# ManitoBoardv_5.net
KiCad netlist of a schematic drawn in EAGLE
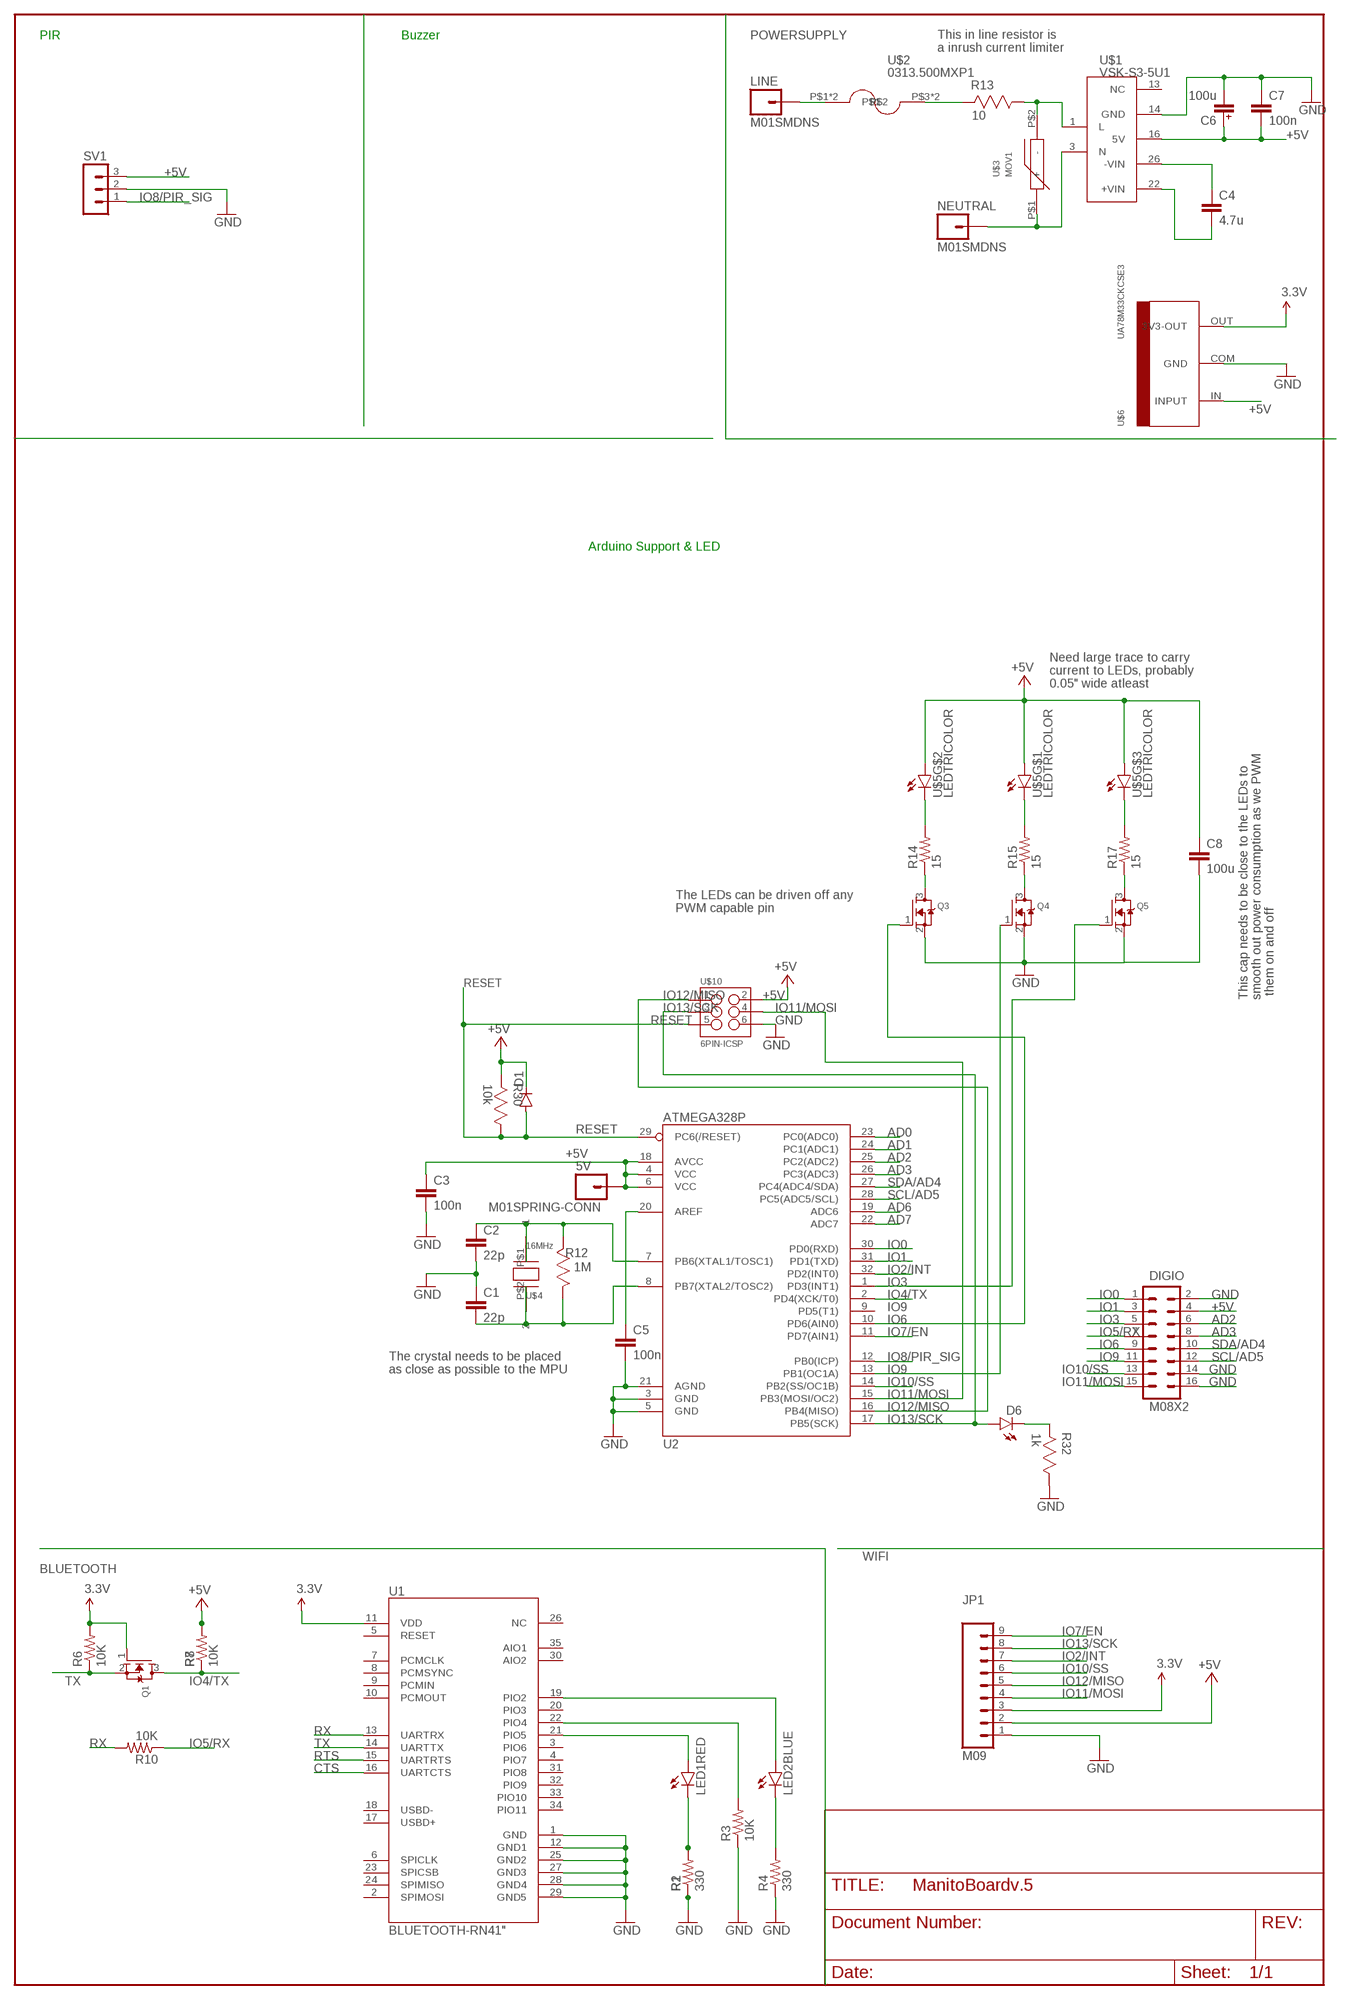
[diagram p0: schematic, sheet 1]

(export (version "E")
  (design (tool "Eeschema 10.0.6"))
  (components
    (comp (ref "5V")
      (value "M01SPRING-CONN")
      (footprint "eagle-import:SPRING-CONNECTOR")
      (libsource (lib "eagle-import") (part "M01SPRING-CONN"))
    )
    (comp (ref "C1")
      (value "22p")
      (footprint "eagle-import:0603-CAP")
      (libsource (lib "eagle-import") (part "CAP0603-CAP"))
    )
    (comp (ref "C2")
      (value "22p")
      (footprint "eagle-import:0603-CAP")
      (libsource (lib "eagle-import") (part "CAP0603-CAP"))
    )
    (comp (ref "C3")
      (value "100n")
      (footprint "eagle-import:0603-CAP")
      (libsource (lib "eagle-import") (part "CAP0603-CAP"))
    )
    (comp (ref "C4")
      (value "4.7u")
      (footprint "eagle-import:0603-CAP")
      (libsource (lib "eagle-import") (part "CAP0603-CAP"))
    )
    (comp (ref "C5")
      (value "100n")
      (footprint "eagle-import:0603-CAP")
      (libsource (lib "eagle-import") (part "CAP0603-CAP"))
    )
    (comp (ref "C6")
      (value "100u")
      (footprint "eagle-import:WXSERIES-SMDCAP")
      (libsource (lib "eagle-import") (part "SMDCAP1"))
    )
    (comp (ref "C7")
      (value "100n")
      (footprint "eagle-import:0603-CAP")
      (libsource (lib "eagle-import") (part "CAP0603-CAP"))
    )
    (comp (ref "C8")
      (value "100u")
      (footprint "eagle-import:0603-CAP")
      (libsource (lib "eagle-import") (part "CAP0603-CAP"))
    )
    (comp (ref "D1")
      (value "DIODE1N4148")
      (footprint "eagle-import:DIODE-1N4148")
      (libsource (lib "eagle-import") (part "DIODE1N4148"))
    )
    (comp (ref "D6")
      (value "LED-YELLOW0603")
      (footprint "eagle-import:LED-0603")
      (libsource (lib "eagle-import") (part "LED-YELLOW0603"))
    )
    (comp (ref "DIGIO")
      (value "M08X2")
      (footprint "eagle-import:2X8")
      (libsource (lib "eagle-import") (part "M08X2"))
    )
    (comp (ref "JP1")
      (value "M09")
      (footprint "eagle-import:1X09")
      (libsource (lib "eagle-import") (part "M09"))
    )
    (comp (ref "LED1RED")
      (value "LED3MM")
      (footprint "eagle-import:LED3MM")
      (libsource (lib "eagle-import") (part "LED3MM"))
    )
    (comp (ref "LED2BLUE")
      (value "LED3MM")
      (footprint "eagle-import:LED3MM")
      (libsource (lib "eagle-import") (part "LED3MM"))
    )
    (comp (ref "LINE")
      (value "M01SMDNS")
      (footprint "eagle-import:1X01NS")
      (libsource (lib "eagle-import") (part "M01SMDNS"))
    )
    (comp (ref "NEUTRAL")
      (value "M01SMDNS")
      (footprint "eagle-import:1X01NS")
      (libsource (lib "eagle-import") (part "M01SMDNS"))
    )
    (comp (ref "Q1")
      (value "MOSFET-NREFLOW")
      (footprint "eagle-import:SOT23")
      (libsource (lib "eagle-import") (part "adafruit_MOSFET-NREFLOW"))
    )
    (comp (ref "Q3")
      (value "MOSFET-NREFLOW")
      (footprint "eagle-import:SOT23")
      (libsource (lib "eagle-import") (part "MOSFET-NREFLOW"))
    )
    (comp (ref "Q4")
      (value "MOSFET-NREFLOW")
      (footprint "eagle-import:SOT23")
      (libsource (lib "eagle-import") (part "MOSFET-NREFLOW"))
    )
    (comp (ref "Q5")
      (value "MOSFET-NREFLOW")
      (footprint "eagle-import:SOT23")
      (libsource (lib "eagle-import") (part "MOSFET-NREFLOW"))
    )
    (comp (ref "R1")
      (value "RESISTORPTH-1/4W")
      (footprint "eagle-import:AXIAL-0.4")
      (libsource (lib "eagle-import") (part "RESISTORPTH-1/4W"))
    )
    (comp (ref "R2")
      (value "330")
      (footprint "eagle-import:AXIAL-0.4")
      (libsource (lib "eagle-import") (part "RESISTORPTH-1/4W"))
    )
    (comp (ref "R3")
      (value "10K")
      (footprint "eagle-import:AXIAL-0.4")
      (libsource (lib "eagle-import") (part "RESISTORPTH-1/4W"))
    )
    (comp (ref "R4")
      (value "330")
      (footprint "eagle-import:AXIAL-0.4")
      (libsource (lib "eagle-import") (part "RESISTORPTH-1/4W"))
    )
    (comp (ref "R6")
      (value "10K")
      (footprint "eagle-import:AXIAL-0.5")
      (libsource (lib "eagle-import") (part "RESISTORPTH-1/2W"))
    )
    (comp (ref "R7")
      (value "RESISTORPTH-1/2W")
      (footprint "eagle-import:AXIAL-0.5")
      (libsource (lib "eagle-import") (part "RESISTORPTH-1/2W"))
    )
    (comp (ref "R8")
      (value "10K")
      (footprint "eagle-import:AXIAL-0.5")
      (libsource (lib "eagle-import") (part "RESISTORPTH-1/2W"))
    )
    (comp (ref "R10")
      (value "10K")
      (footprint "eagle-import:AXIAL-0.5")
      (libsource (lib "eagle-import") (part "RESISTORPTH-1/2W"))
    )
    (comp (ref "R12")
      (value "1M")
      (footprint "eagle-import:0603RESISTOR")
      (fields (field (name "MPN") "CRCW06031K21FKEA") (field (name "TOLERANCE") "± 1.0 %"))
      (libsource (lib "eagle-import") (part "0603RESISTOR1"))
    )
    (comp (ref "R13")
      (value "10")
      (footprint "eagle-import:0603RESISTOR")
      (fields (field (name "MPN") "CRCW06031K21FKEA") (field (name "TOLERANCE") "± 1.0 %"))
      (libsource (lib "eagle-import") (part "0603RESISTOR1"))
    )
    (comp (ref "R14")
      (value "15")
      (footprint "eagle-import:AXIAL-0.6")
      (libsource (lib "eagle-import") (part "RESISTORPTH-1W"))
    )
    (comp (ref "R15")
      (value "15")
      (footprint "eagle-import:AXIAL-0.6")
      (libsource (lib "eagle-import") (part "RESISTORPTH-1W"))
    )
    (comp (ref "R17")
      (value "15")
      (footprint "eagle-import:AXIAL-0.6")
      (libsource (lib "eagle-import") (part "RESISTORPTH-1W"))
    )
    (comp (ref "R30")
      (value "10k")
      (footprint "eagle-import:0603RESISTOR")
      (fields (field (name "MPN") "CRCW06031K21FKEA") (field (name "TOLERANCE") "± 1.0 %"))
      (libsource (lib "eagle-import") (part "0603RESISTOR1"))
    )
    (comp (ref "R32")
      (value "1k")
      (footprint "eagle-import:0603RESISTOR")
      (fields (field (name "MPN") "CRCW06031K21FKEA") (field (name "TOLERANCE") "± 1.0 %"))
      (libsource (lib "eagle-import") (part "0603RESISTOR1"))
    )
    (comp (ref "SV1")
      (value "MA03-1")
      (footprint "eagle-import:MA03-1")
      (libsource (lib "eagle-import") (part "MA03-1"))
    )
    (comp (ref "U$1")
      (value "VSK-S3-5U1")
      (footprint "eagle-import:VSK-S3-DCAC")
      (libsource (lib "eagle-import") (part "VSK-S3-5U1"))
    )
    (comp (ref "U$2")
      (value "0313.500MXP1")
      (footprint "eagle-import:FUSEHOLDER0.25IN")
      (libsource (lib "eagle-import") (part "0313.500MXP1"))
    )
    (comp (ref "U$3")
      (value "MOV1")
      (footprint "eagle-import:MOV")
      (libsource (lib "eagle-import") (part "MOV1"))
    )
    (comp (ref "U$4")
      (value "16MHz")
      (footprint "eagle-import:SMDCRYSTAL")
      (libsource (lib "eagle-import") (part "SMDCRYSTAL"))
    )
    (comp (ref "U$5")
      (value "LEDTRICOLOR")
      (footprint "eagle-import:TRICOLORLED")
      (libsource (lib "eagle-import") (part "LEDTRICOLOR"))
    )
    (comp (ref "U$6")
      (value "UA78M33CKCSE3")
      (footprint "eagle-import:TO220")
      (libsource (lib "eagle-import") (part "UA78M33CKCSE3"))
    )
    (comp (ref "U$10")
      (value "6PIN-ICSP")
      (footprint "eagle-import:2X3-ICSP")
      (libsource (lib "eagle-import") (part "6PIN-ICSP"))
    )
    (comp (ref "U1")
      (value "BLUETOOTH-RN41\"")
      (footprint "eagle-import:RN41")
      (libsource (lib "eagle-import") (part "BLUETOOTH-RN41{dblquote}"))
    )
    (comp (ref "U2")
      (value "ATMEGA328P")
      (footprint "eagle-import:TQFP32-08")
      (libsource (lib "eagle-import") (part "ATMEGA328_SMT"))
    )
  )
  (nets
    (net (code "1") (name "+5V") (class "Default")
      (node (ref "5V") (pin "P$2") (pinfunction "1_P$2") (pintype "passive"))
      (node (ref "C3") (pin "1") (pinfunction "1_1") (pintype "passive"))
      (node (ref "C6") (pin "POS") (pinfunction "POS_POS") (pintype "passive"))
      (node (ref "C7") (pin "2") (pinfunction "2_2") (pintype "passive"))
      (node (ref "C8") (pin "1") (pinfunction "1_1") (pintype "passive"))
      (node (ref "D1") (pin "C") (pinfunction "C_C") (pintype "passive"))
      (node (ref "DIGIO") (pin "4") (pinfunction "4_4") (pintype "passive"))
      (node (ref "JP1") (pin "2") (pinfunction "2_2") (pintype "passive"))
      (node (ref "R30") (pin "2") (pinfunction "2_2") (pintype "passive"))
      (node (ref "R7") (pin "P$2") (pinfunction "2_P$2") (pintype "passive"))
      (node (ref "R8") (pin "P$2") (pinfunction "2_P$2") (pintype "passive"))
      (node (ref "SV1") (pin "3") (pinfunction "3_3") (pintype "passive"))
      (node (ref "U$1") (pin "16") (pinfunction "5V_16") (pintype "bidirectional"))
      (node (ref "U$10") (pin "2") (pinfunction "+5V_2") (pintype "power_in"))
      (node (ref "U$5") (pin "A1") (pinfunction "A_A1") (pintype "passive"))
      (node (ref "U$5") (pin "A2") (pinfunction "A_A2") (pintype "passive"))
      (node (ref "U$5") (pin "A3") (pinfunction "A_A3") (pintype "passive"))
      (node (ref "U$6") (pin "IN") (pinfunction "INPUT_IN") (pintype "power_in"))
      (node (ref "U2") (pin "18") (pinfunction "AVCC_18") (pintype "bidirectional"))
      (node (ref "U2") (pin "4") (pinfunction "VCC_4") (pintype "bidirectional"))
      (node (ref "U2") (pin "6") (pinfunction "VCC_6") (pintype "bidirectional"))
    )
    (net (code "2") (name "/AD0") (class "Default")
      (node (ref "U2") (pin "23") (pinfunction "PC0(ADC0)_23") (pintype "bidirectional"))
    )
    (net (code "3") (name "/AD1") (class "Default")
      (node (ref "U2") (pin "24") (pinfunction "PC1(ADC1)_24") (pintype "bidirectional"))
    )
    (net (code "4") (name "/AD2") (class "Default")
      (node (ref "DIGIO") (pin "6") (pinfunction "6_6") (pintype "passive"))
      (node (ref "U2") (pin "25") (pinfunction "PC2(ADC2)_25") (pintype "bidirectional"))
    )
    (net (code "5") (name "/AD3") (class "Default")
      (node (ref "DIGIO") (pin "8") (pinfunction "8_8") (pintype "passive"))
      (node (ref "U2") (pin "26") (pinfunction "PC3(ADC3)_26") (pintype "bidirectional"))
    )
    (net (code "6") (name "/AD6") (class "Default")
      (node (ref "U2") (pin "19") (pinfunction "ADC6_19") (pintype "bidirectional"))
    )
    (net (code "7") (name "/AD7") (class "Default")
      (node (ref "U2") (pin "22") (pinfunction "ADC7_22") (pintype "bidirectional"))
    )
    (net (code "9") (name "/CTS") (class "Default")
      (node (ref "U1") (pin "16") (pinfunction "UARTCTS_16") (pintype "bidirectional"))
    )
    (net (code "10") (name "/IO0") (class "Default")
      (node (ref "DIGIO") (pin "1") (pinfunction "1_1") (pintype "passive"))
      (node (ref "U2") (pin "30") (pinfunction "PD0(RXD)_30") (pintype "bidirectional"))
    )
    (net (code "11") (name "/IO1") (class "Default")
      (node (ref "DIGIO") (pin "3") (pinfunction "3_3") (pintype "passive"))
      (node (ref "U2") (pin "31") (pinfunction "PD1(TXD)_31") (pintype "bidirectional"))
    )
    (net (code "12") (name "/IO2{slash}INT") (class "Default")
      (node (ref "JP1") (pin "7") (pinfunction "7_7") (pintype "passive"))
      (node (ref "U2") (pin "32") (pinfunction "PD2(INT0)_32") (pintype "bidirectional"))
    )
    (net (code "13") (name "/IO3") (class "Default")
      (node (ref "DIGIO") (pin "5") (pinfunction "5_5") (pintype "passive"))
      (node (ref "Q5") (pin "1") (pinfunction "G_1") (pintype "bidirectional"))
      (node (ref "U2") (pin "1") (pinfunction "PD3(INT1)_1") (pintype "bidirectional"))
    )
    (net (code "14") (name "/IO4{slash}TX") (class "Default")
      (node (ref "Q1") (pin "3") (pinfunction "D_3") (pintype "bidirectional"))
      (node (ref "R7") (pin "P$1") (pinfunction "1_P$1") (pintype "passive"))
      (node (ref "R8") (pin "P$1") (pinfunction "1_P$1") (pintype "passive"))
      (node (ref "U2") (pin "2") (pinfunction "PD4(XCK/T0)_2") (pintype "bidirectional"))
    )
    (net (code "15") (name "/IO5{slash}RX") (class "Default")
      (node (ref "DIGIO") (pin "7") (pinfunction "7_7") (pintype "passive"))
      (node (ref "R10") (pin "P$1") (pinfunction "1_P$1") (pintype "passive"))
    )
    (net (code "16") (name "/IO6") (class "Default")
      (node (ref "DIGIO") (pin "9") (pinfunction "9_9") (pintype "passive"))
      (node (ref "Q3") (pin "1") (pinfunction "G_1") (pintype "bidirectional"))
      (node (ref "U2") (pin "10") (pinfunction "PD6(AIN0)_10") (pintype "bidirectional"))
    )
    (net (code "17") (name "/IO7{slash}EN") (class "Default")
      (node (ref "JP1") (pin "9") (pinfunction "9_9") (pintype "passive"))
      (node (ref "U2") (pin "11") (pinfunction "PD7(AIN1)_11") (pintype "bidirectional"))
    )
    (net (code "18") (name "/IO8{slash}PIR_SIG") (class "Default")
      (node (ref "SV1") (pin "1") (pinfunction "1_1") (pintype "passive"))
      (node (ref "U2") (pin "12") (pinfunction "PB0(ICP)_12") (pintype "bidirectional"))
    )
    (net (code "19") (name "/IO9") (class "Default")
      (node (ref "DIGIO") (pin "11") (pinfunction "11_11") (pintype "passive"))
      (node (ref "Q4") (pin "1") (pinfunction "G_1") (pintype "bidirectional"))
      (node (ref "U2") (pin "13") (pinfunction "PB1(OC1A)_13") (pintype "bidirectional"))
    )
    (net (code "20") (name "/IO10{slash}SS") (class "Default")
      (node (ref "DIGIO") (pin "13") (pinfunction "13_13") (pintype "passive"))
      (node (ref "JP1") (pin "6") (pinfunction "6_6") (pintype "passive"))
      (node (ref "U2") (pin "14") (pinfunction "PB2(SS/OC1B)_14") (pintype "bidirectional"))
    )
    (net (code "21") (name "/IO11{slash}MOSI") (class "Default")
      (node (ref "DIGIO") (pin "15") (pinfunction "15_15") (pintype "passive"))
      (node (ref "JP1") (pin "4") (pinfunction "4_4") (pintype "passive"))
      (node (ref "U$10") (pin "4") (pinfunction "MOSI_4") (pintype "bidirectional"))
      (node (ref "U2") (pin "15") (pinfunction "PB3(MOSI/OC2)_15") (pintype "bidirectional"))
    )
    (net (code "22") (name "/IO12{slash}MISO") (class "Default")
      (node (ref "JP1") (pin "5") (pinfunction "5_5") (pintype "passive"))
      (node (ref "U$10") (pin "1") (pinfunction "MISO_1") (pintype "bidirectional"))
      (node (ref "U2") (pin "16") (pinfunction "PB4(MISO)_16") (pintype "bidirectional"))
    )
    (net (code "23") (name "/IO13{slash}SCK") (class "Default")
      (node (ref "D6") (pin "A") (pinfunction "A_A") (pintype "passive"))
      (node (ref "JP1") (pin "8") (pinfunction "8_8") (pintype "passive"))
      (node (ref "U$10") (pin "3") (pinfunction "SCK_3") (pintype "bidirectional"))
      (node (ref "U2") (pin "17") (pinfunction "PB5(SCK)_17") (pintype "bidirectional"))
    )
    (net (code "25") (name "/RESET") (class "Default")
      (node (ref "D1") (pin "A") (pinfunction "A_A") (pintype "passive"))
      (node (ref "R30") (pin "1") (pinfunction "1_1") (pintype "passive"))
      (node (ref "U$10") (pin "5") (pinfunction "RESET_5") (pintype "bidirectional"))
      (node (ref "U2") (pin "29") (pinfunction "PC6(/RESET)_29") (pintype "bidirectional"))
    )
    (net (code "26") (name "/RTS") (class "Default")
      (node (ref "U1") (pin "15") (pinfunction "UARTRTS_15") (pintype "bidirectional"))
    )
    (net (code "27") (name "/RX") (class "Default")
      (node (ref "R10") (pin "P$2") (pinfunction "2_P$2") (pintype "passive"))
      (node (ref "U1") (pin "13") (pinfunction "UARTRX_13") (pintype "bidirectional"))
    )
    (net (code "28") (name "/SCL{slash}AD5") (class "Default")
      (node (ref "DIGIO") (pin "12") (pinfunction "12_12") (pintype "passive"))
      (node (ref "U2") (pin "28") (pinfunction "PC5(ADC5/SCL)_28") (pintype "bidirectional"))
    )
    (net (code "29") (name "/SDA{slash}AD4") (class "Default")
      (node (ref "DIGIO") (pin "10") (pinfunction "10_10") (pintype "passive"))
      (node (ref "U2") (pin "27") (pinfunction "PC4(ADC4/SDA)_27") (pintype "bidirectional"))
    )
    (net (code "30") (name "/TX") (class "Default")
      (node (ref "Q1") (pin "2") (pinfunction "S_2") (pintype "bidirectional"))
      (node (ref "R6") (pin "P$1") (pinfunction "1_P$1") (pintype "passive"))
      (node (ref "U1") (pin "14") (pinfunction "UARTTX_14") (pintype "bidirectional"))
    )
    (net (code "32") (name "3.3V") (class "Default")
      (node (ref "JP1") (pin "3") (pinfunction "3_3") (pintype "passive"))
      (node (ref "Q1") (pin "1") (pinfunction "G_1") (pintype "bidirectional"))
      (node (ref "R6") (pin "P$2") (pinfunction "2_P$2") (pintype "passive"))
      (node (ref "U$6") (pin "OUT") (pinfunction "3V3-OUT_OUT") (pintype "power_in"))
      (node (ref "U1") (pin "11") (pinfunction "VDD_11") (pintype "bidirectional"))
    )
    (net (code "33") (name "GND") (class "Default")
      (node (ref "C1") (pin "1") (pinfunction "1_1") (pintype "passive"))
      (node (ref "C2") (pin "2") (pinfunction "2_2") (pintype "passive"))
      (node (ref "C3") (pin "2") (pinfunction "2_2") (pintype "passive"))
      (node (ref "C5") (pin "2") (pinfunction "2_2") (pintype "passive"))
      (node (ref "C6") (pin "NEG") (pinfunction "NEG_NEG") (pintype "passive"))
      (node (ref "C7") (pin "1") (pinfunction "1_1") (pintype "passive"))
      (node (ref "C8") (pin "2") (pinfunction "2_2") (pintype "passive"))
      (node (ref "DIGIO") (pin "14") (pinfunction "14_14") (pintype "passive"))
      (node (ref "DIGIO") (pin "16") (pinfunction "16_16") (pintype "passive"))
      (node (ref "DIGIO") (pin "2") (pinfunction "2_2") (pintype "passive"))
      (node (ref "JP1") (pin "1") (pinfunction "1_1") (pintype "passive"))
      (node (ref "Q3") (pin "2") (pinfunction "S_2") (pintype "bidirectional"))
      (node (ref "Q4") (pin "2") (pinfunction "S_2") (pintype "bidirectional"))
      (node (ref "Q5") (pin "2") (pinfunction "S_2") (pintype "bidirectional"))
      (node (ref "R1") (pin "P$1") (pinfunction "1_P$1") (pintype "passive"))
      (node (ref "R2") (pin "P$1") (pinfunction "1_P$1") (pintype "passive"))
      (node (ref "R3") (pin "P$1") (pinfunction "1_P$1") (pintype "passive"))
      (node (ref "R32") (pin "1") (pinfunction "1_1") (pintype "passive"))
      (node (ref "R4") (pin "P$1") (pinfunction "1_P$1") (pintype "passive"))
      (node (ref "SV1") (pin "2") (pinfunction "2_2") (pintype "passive"))
      (node (ref "U$1") (pin "14") (pinfunction "GND_14") (pintype "bidirectional"))
      (node (ref "U$10") (pin "6") (pinfunction "GND_6") (pintype "power_in"))
      (node (ref "U$6") (pin "COM") (pinfunction "GND_COM") (pintype "power_in"))
      (node (ref "U1") (pin "1") (pinfunction "GND_1") (pintype "bidirectional"))
      (node (ref "U1") (pin "12") (pinfunction "GND1_12") (pintype "bidirectional"))
      (node (ref "U1") (pin "25") (pinfunction "GND2_25") (pintype "bidirectional"))
      (node (ref "U1") (pin "27") (pinfunction "GND3_27") (pintype "bidirectional"))
      (node (ref "U1") (pin "28") (pinfunction "GND4_28") (pintype "bidirectional"))
      (node (ref "U1") (pin "29") (pinfunction "GND5_29") (pintype "bidirectional"))
      (node (ref "U2") (pin "21") (pinfunction "AGND_21") (pintype "bidirectional"))
      (node (ref "U2") (pin "3") (pinfunction "GND_3") (pintype "bidirectional"))
      (node (ref "U2") (pin "5") (pinfunction "GND_5") (pintype "bidirectional"))
    )
    (net (code "34") (name "Net-(D6-PadC)") (class "Default")
      (node (ref "D6") (pin "C") (pinfunction "C_C") (pintype "passive"))
      (node (ref "R32") (pin "2") (pinfunction "2_2") (pintype "passive"))
    )
    (net (code "35") (name "Net-(LED1RED-C)") (class "Default")
      (node (ref "LED1RED") (pin "K") (pinfunction "C_K") (pintype "passive"))
      (node (ref "R1") (pin "P$2") (pinfunction "2_P$2") (pintype "passive"))
      (node (ref "R2") (pin "P$2") (pinfunction "2_P$2") (pintype "passive"))
    )
    (net (code "36") (name "Net-(LED2BLUE-C)") (class "Default")
      (node (ref "LED2BLUE") (pin "K") (pinfunction "C_K") (pintype "passive"))
      (node (ref "R4") (pin "P$2") (pinfunction "2_P$2") (pintype "passive"))
    )
    (net (code "37") (name "Net-(LINE-Pad1)") (class "Default")
      (node (ref "LINE") (pin "1") (pinfunction "1_1") (pintype "passive"))
      (node (ref "U$2") (pin "P$1") (pinfunction "P$1_P$1") (pintype "bidirectional"))
      (node (ref "U$2") (pin "P$2") (pinfunction "P$1_P$2") (pintype "bidirectional"))
    )
    (net (code "38") (name "Net-(Q3-D)") (class "Default")
      (node (ref "Q3") (pin "3") (pinfunction "D_3") (pintype "bidirectional"))
      (node (ref "R14") (pin "P$1") (pinfunction "1_P$1") (pintype "passive"))
    )
    (net (code "39") (name "Net-(Q4-D)") (class "Default")
      (node (ref "Q4") (pin "3") (pinfunction "D_3") (pintype "bidirectional"))
      (node (ref "R15") (pin "P$1") (pinfunction "1_P$1") (pintype "passive"))
    )
    (net (code "40") (name "Net-(Q5-D)") (class "Default")
      (node (ref "Q5") (pin "3") (pinfunction "D_3") (pintype "bidirectional"))
      (node (ref "R17") (pin "P$1") (pinfunction "1_P$1") (pintype "passive"))
    )
    (net (code "41") (name "Net-(R3-2)") (class "Default")
      (node (ref "R3") (pin "P$2") (pinfunction "2_P$2") (pintype "passive"))
      (node (ref "U1") (pin "22") (pinfunction "PIO4_22") (pintype "bidirectional"))
    )
    (net (code "42") (name "Net-(R13-Pad2)") (class "Default")
      (node (ref "R13") (pin "2") (pinfunction "2_2") (pintype "passive"))
      (node (ref "U$2") (pin "P$3") (pinfunction "P$2_P$3") (pintype "bidirectional"))
      (node (ref "U$2") (pin "P$4") (pinfunction "P$2_P$4") (pintype "bidirectional"))
    )
    (net (code "43") (name "Net-(R14-2)") (class "Default")
      (node (ref "R14") (pin "P$2") (pinfunction "2_P$2") (pintype "passive"))
      (node (ref "U$5") (pin "C2") (pinfunction "C_C2") (pintype "passive"))
    )
    (net (code "44") (name "Net-(R15-2)") (class "Default")
      (node (ref "R15") (pin "P$2") (pinfunction "2_P$2") (pintype "passive"))
      (node (ref "U$5") (pin "C1") (pinfunction "C_C1") (pintype "passive"))
    )
    (net (code "45") (name "Net-(R17-2)") (class "Default")
      (node (ref "R17") (pin "P$2") (pinfunction "2_P$2") (pintype "passive"))
      (node (ref "U$5") (pin "C3") (pinfunction "C_C3") (pintype "passive"))
    )
    (net (code "46") (name "Net-(U$1-+VIN)") (class "Default")
      (node (ref "C4") (pin "2") (pinfunction "2_2") (pintype "passive"))
      (node (ref "U$1") (pin "22") (pinfunction "+VIN_22") (pintype "bidirectional"))
    )
    (net (code "47") (name "Net-(U$1--VIN)") (class "Default")
      (node (ref "C4") (pin "1") (pinfunction "1_1") (pintype "passive"))
      (node (ref "U$1") (pin "26") (pinfunction "-VIN_26") (pintype "bidirectional"))
    )
    (net (code "48") (name "Net-(U$1-L)") (class "Default")
      (node (ref "R13") (pin "1") (pinfunction "1_1") (pintype "passive"))
      (node (ref "U$1") (pin "1") (pinfunction "L_1") (pintype "bidirectional"))
      (node (ref "U$3") (pin "P$2") (pinfunction "-_P$2") (pintype "bidirectional"))
    )
    (net (code "49") (name "Net-(U$1-N)") (class "Default")
      (node (ref "NEUTRAL") (pin "1") (pinfunction "1_1") (pintype "passive"))
      (node (ref "U$1") (pin "3") (pinfunction "N_3") (pintype "bidirectional"))
      (node (ref "U$3") (pin "P$1") (pinfunction "+_P$1") (pintype "bidirectional"))
    )
    (net (code "50") (name "Net-(U$4-1)") (class "Default")
      (node (ref "C2") (pin "1") (pinfunction "1_1") (pintype "passive"))
      (node (ref "R12") (pin "2") (pinfunction "2_2") (pintype "passive"))
      (node (ref "U$4") (pin "P$1") (pinfunction "1_P$1") (pintype "bidirectional"))
      (node (ref "U2") (pin "7") (pinfunction "PB6(XTAL1/TOSC1)_7") (pintype "bidirectional"))
    )
    (net (code "51") (name "Net-(U$4-2)") (class "Default")
      (node (ref "C1") (pin "2") (pinfunction "2_2") (pintype "passive"))
      (node (ref "R12") (pin "1") (pinfunction "1_1") (pintype "passive"))
      (node (ref "U$4") (pin "P$2") (pinfunction "2_P$2") (pintype "bidirectional"))
      (node (ref "U2") (pin "8") (pinfunction "PB7(XTAL2/TOSC2)_8") (pintype "bidirectional"))
    )
    (net (code "52") (name "Net-(U1-PIO2)") (class "Default")
      (node (ref "LED2BLUE") (pin "A") (pinfunction "A_A") (pintype "passive"))
      (node (ref "U1") (pin "19") (pinfunction "PIO2_19") (pintype "bidirectional"))
    )
    (net (code "53") (name "Net-(U1-PIO5)") (class "Default")
      (node (ref "LED1RED") (pin "A") (pinfunction "A_A") (pintype "passive"))
      (node (ref "U1") (pin "21") (pinfunction "PIO5_21") (pintype "bidirectional"))
    )
    (net (code "54") (name "Net-(U2-AREF)") (class "Default")
      (node (ref "C5") (pin "1") (pinfunction "1_1") (pintype "passive"))
      (node (ref "U2") (pin "20") (pinfunction "AREF_20") (pintype "bidirectional"))
    )
    (net (code "55") (name "unconnected-(U$1-NC-Pad13)") (class "Default")
      (node (ref "U$1") (pin "13") (pinfunction "NC_13") (pintype "no_connect"))
    )
    (net (code "56") (name "unconnected-(U1-AIO1-Pad35)") (class "Default")
      (node (ref "U1") (pin "35") (pinfunction "AIO1_35") (pintype "bidirectional"))
    )
    (net (code "57") (name "unconnected-(U1-AIO2-Pad30)") (class "Default")
      (node (ref "U1") (pin "30") (pinfunction "AIO2_30") (pintype "bidirectional"))
    )
    (net (code "58") (name "unconnected-(U1-NC-Pad26)") (class "Default")
      (node (ref "U1") (pin "26") (pinfunction "NC_26") (pintype "bidirectional"))
    )
    (net (code "59") (name "unconnected-(U1-PCMCLK-Pad7)") (class "Default")
      (node (ref "U1") (pin "7") (pinfunction "PCMCLK_7") (pintype "bidirectional"))
    )
    (net (code "60") (name "unconnected-(U1-PCMIN-Pad9)") (class "Default")
      (node (ref "U1") (pin "9") (pinfunction "PCMIN_9") (pintype "bidirectional"))
    )
    (net (code "61") (name "unconnected-(U1-PCMOUT-Pad10)") (class "Default")
      (node (ref "U1") (pin "10") (pinfunction "PCMOUT_10") (pintype "bidirectional"))
    )
    (net (code "62") (name "unconnected-(U1-PCMSYNC-Pad8)") (class "Default")
      (node (ref "U1") (pin "8") (pinfunction "PCMSYNC_8") (pintype "bidirectional"))
    )
    (net (code "63") (name "unconnected-(U1-PIO3-Pad20)") (class "Default")
      (node (ref "U1") (pin "20") (pinfunction "PIO3_20") (pintype "bidirectional"))
    )
    (net (code "64") (name "unconnected-(U1-PIO6-Pad3)") (class "Default")
      (node (ref "U1") (pin "3") (pinfunction "PIO6_3") (pintype "bidirectional"))
    )
    (net (code "65") (name "unconnected-(U1-PIO7-Pad4)") (class "Default")
      (node (ref "U1") (pin "4") (pinfunction "PIO7_4") (pintype "bidirectional"))
    )
    (net (code "66") (name "unconnected-(U1-PIO8-Pad31)") (class "Default")
      (node (ref "U1") (pin "31") (pinfunction "PIO8_31") (pintype "bidirectional"))
    )
    (net (code "67") (name "unconnected-(U1-PIO9-Pad32)") (class "Default")
      (node (ref "U1") (pin "32") (pinfunction "PIO9_32") (pintype "bidirectional"))
    )
    (net (code "68") (name "unconnected-(U1-PIO10-Pad33)") (class "Default")
      (node (ref "U1") (pin "33") (pinfunction "PIO10_33") (pintype "bidirectional"))
    )
    (net (code "69") (name "unconnected-(U1-PIO11-Pad34)") (class "Default")
      (node (ref "U1") (pin "34") (pinfunction "PIO11_34") (pintype "bidirectional"))
    )
    (net (code "70") (name "unconnected-(U1-RESET-Pad5)") (class "Default")
      (node (ref "U1") (pin "5") (pinfunction "RESET_5") (pintype "bidirectional"))
    )
    (net (code "71") (name "unconnected-(U1-SPICLK-Pad6)") (class "Default")
      (node (ref "U1") (pin "6") (pinfunction "SPICLK_6") (pintype "bidirectional"))
    )
    (net (code "72") (name "unconnected-(U1-SPICSB-Pad23)") (class "Default")
      (node (ref "U1") (pin "23") (pinfunction "SPICSB_23") (pintype "bidirectional"))
    )
    (net (code "73") (name "unconnected-(U1-SPIMISO-Pad24)") (class "Default")
      (node (ref "U1") (pin "24") (pinfunction "SPIMISO_24") (pintype "bidirectional"))
    )
    (net (code "74") (name "unconnected-(U1-SPIMOSI-Pad2)") (class "Default")
      (node (ref "U1") (pin "2") (pinfunction "SPIMOSI_2") (pintype "bidirectional"))
    )
    (net (code "75") (name "unconnected-(U1-USBD+-Pad17)") (class "Default")
      (node (ref "U1") (pin "17") (pinfunction "USBD+_17") (pintype "bidirectional"))
    )
    (net (code "76") (name "unconnected-(U1-USBD--Pad18)") (class "Default")
      (node (ref "U1") (pin "18") (pinfunction "USBD-_18") (pintype "bidirectional"))
    )
    (net (code "77") (name "unconnected-(U2-PD5(T1)-Pad9)") (class "Default")
      (node (ref "U2") (pin "9") (pinfunction "PD5(T1)_9") (pintype "bidirectional"))
    )
  )
)
